# Sonar_Power_Schematic_LT1962.net
KiCad netlist of a schematic drawn in EAGLE
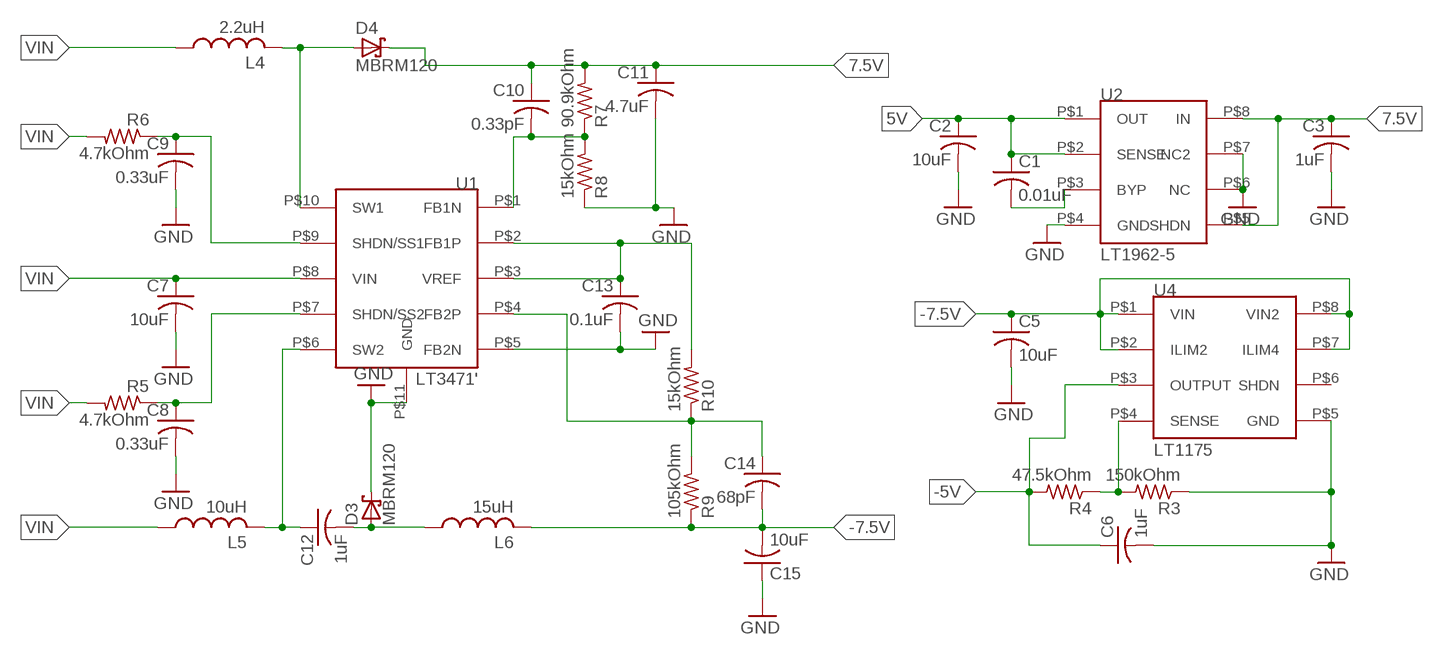
[diagram p0: schematic, sheet 1]

(export (version "E")
  (design (tool "Eeschema 10.0.6"))
  (components
    (comp (ref "C1")
      (value "0.01uF")
      (footprint "eagle-import:C0603")
      (libsource (lib "eagle-import") (part "C-USC0603"))
    )
    (comp (ref "C2")
      (value "10uF")
      (footprint "eagle-import:C0603")
      (libsource (lib "eagle-import") (part "C-USC0603"))
    )
    (comp (ref "C3")
      (value "1uF")
      (footprint "eagle-import:C0603")
      (libsource (lib "eagle-import") (part "C-USC0603"))
    )
    (comp (ref "C5")
      (value "10uF")
      (footprint "eagle-import:C0603")
      (libsource (lib "eagle-import") (part "C-USC0603"))
    )
    (comp (ref "C6")
      (value "1uF")
      (footprint "eagle-import:C0603")
      (libsource (lib "eagle-import") (part "C-USC0603"))
    )
    (comp (ref "C7")
      (value "10uF")
      (footprint "eagle-import:C0603")
      (libsource (lib "eagle-import") (part "C-USC0603"))
    )
    (comp (ref "C8")
      (value "0.33uF")
      (footprint "eagle-import:C0603")
      (libsource (lib "eagle-import") (part "C-USC0603"))
    )
    (comp (ref "C9")
      (value "0.33uF")
      (footprint "eagle-import:C0603")
      (libsource (lib "eagle-import") (part "C-USC0603"))
    )
    (comp (ref "C10")
      (value "0.33pF")
      (footprint "eagle-import:C0603")
      (libsource (lib "eagle-import") (part "C-USC0603"))
    )
    (comp (ref "C11")
      (value "4.7uF")
      (footprint "eagle-import:C0603")
      (libsource (lib "eagle-import") (part "C-USC0603"))
    )
    (comp (ref "C12")
      (value "1uF")
      (footprint "eagle-import:C0603")
      (libsource (lib "eagle-import") (part "C-USC0603"))
    )
    (comp (ref "C13")
      (value "0.1uF")
      (footprint "eagle-import:C0603")
      (libsource (lib "eagle-import") (part "C-USC0603"))
    )
    (comp (ref "C14")
      (value "68pF")
      (footprint "eagle-import:C0603")
      (libsource (lib "eagle-import") (part "C-USC0603"))
    )
    (comp (ref "C15")
      (value "10uF")
      (footprint "eagle-import:C0603")
      (libsource (lib "eagle-import") (part "C-USC0603"))
    )
    (comp (ref "D3")
      (value "MBRM120")
      (footprint "eagle-import:DO-216AA")
      (libsource (lib "eagle-import") (part "MBRM120"))
    )
    (comp (ref "D4")
      (value "MBRM120")
      (footprint "eagle-import:DO-216AA")
      (libsource (lib "eagle-import") (part "MBRM120"))
    )
    (comp (ref "L4")
      (value "2.2uH")
      (footprint "eagle-import:NS4.9X4.9")
      (libsource (lib "eagle-import") (part "LQH5BPN2R2N38L"))
    )
    (comp (ref "L5")
      (value "10uH")
      (footprint "eagle-import:NS5X5")
      (libsource (lib "eagle-import") (part "VLS5045EX-100M2"))
    )
    (comp (ref "L6")
      (value "15uH")
      (footprint "eagle-import:NS5X5")
      (libsource (lib "eagle-import") (part "VLS5045EX-150M-CA1"))
    )
    (comp (ref "R3")
      (value "150kOhm")
      (footprint "eagle-import:R0603")
      (libsource (lib "eagle-import") (part "R-US_R0603"))
    )
    (comp (ref "R4")
      (value "47.5kOhm")
      (footprint "eagle-import:R0603")
      (libsource (lib "eagle-import") (part "R-US_R0603"))
    )
    (comp (ref "R5")
      (value "4.7kOhm")
      (footprint "eagle-import:R0603")
      (libsource (lib "eagle-import") (part "R-US_R0603"))
    )
    (comp (ref "R6")
      (value "4.7kOhm")
      (footprint "eagle-import:R0603")
      (libsource (lib "eagle-import") (part "R-US_R0603"))
    )
    (comp (ref "R7")
      (value "90.9kOhm")
      (footprint "eagle-import:R0603")
      (libsource (lib "eagle-import") (part "R-US_R0603"))
    )
    (comp (ref "R8")
      (value "15kOhm")
      (footprint "eagle-import:R0603")
      (libsource (lib "eagle-import") (part "R-US_R0603"))
    )
    (comp (ref "R9")
      (value "105kOhm")
      (footprint "eagle-import:R0603")
      (libsource (lib "eagle-import") (part "R-US_R0603"))
    )
    (comp (ref "R10")
      (value "15kOhm")
      (footprint "eagle-import:R0603")
      (libsource (lib "eagle-import") (part "R-US_R0603"))
    )
    (comp (ref "U1")
      (value "LT3471'")
      (footprint "eagle-import:10-WFDFN")
      (libsource (lib "eagle-import") (part "LT3471'"))
    )
    (comp (ref "U2")
      (value "LT1962-5")
      (footprint "eagle-import:8-MSOP")
      (libsource (lib "eagle-import") (part "LT1962-5"))
    )
    (comp (ref "U4")
      (value "LT1175")
      (footprint "eagle-import:8-SOIC")
      (libsource (lib "eagle-import") (part "LT1175"))
    )
  )
  (nets
    (net (code "1") (name "-5V") (class "Default")
      (node (ref "C6") (pin "1") (pinfunction "1_1") (pintype "passive"))
      (node (ref "R4") (pin "2") (pinfunction "2_2") (pintype "passive"))
      (node (ref "U4") (pin "P$3") (pinfunction "OUTPUT_P$3") (pintype "bidirectional"))
    )
    (net (code "2") (name "-7.5V") (class "Default")
      (node (ref "C14") (pin "2") (pinfunction "2_2") (pintype "passive"))
      (node (ref "C15") (pin "2") (pinfunction "2_2") (pintype "passive"))
      (node (ref "C5") (pin "1") (pinfunction "1_1") (pintype "passive"))
      (node (ref "L6") (pin "P$2") (pinfunction "2_P$2") (pintype "passive"))
      (node (ref "R9") (pin "1") (pinfunction "1_1") (pintype "passive"))
      (node (ref "U4") (pin "P$1") (pinfunction "VIN_P$1") (pintype "power_in"))
      (node (ref "U4") (pin "P$2") (pinfunction "ILIM2_P$2") (pintype "bidirectional"))
      (node (ref "U4") (pin "P$7") (pinfunction "ILIM4_P$7") (pintype "bidirectional"))
      (node (ref "U4") (pin "P$8") (pinfunction "VIN2_P$8") (pintype "power_in"))
    )
    (net (code "3") (name "5V") (class "Default")
      (node (ref "C1") (pin "1") (pinfunction "1_1") (pintype "passive"))
      (node (ref "C2") (pin "1") (pinfunction "1_1") (pintype "passive"))
      (node (ref "U2") (pin "P$1") (pinfunction "OUT_P$1") (pintype "bidirectional"))
      (node (ref "U2") (pin "P$2") (pinfunction "SENSE_P$2") (pintype "bidirectional"))
    )
    (net (code "4") (name "7.5V") (class "Default")
      (node (ref "C10") (pin "1") (pinfunction "1_1") (pintype "passive"))
      (node (ref "C11") (pin "1") (pinfunction "1_1") (pintype "passive"))
      (node (ref "C3") (pin "1") (pinfunction "1_1") (pintype "passive"))
      (node (ref "D4") (pin "P$1") (pinfunction "C_P$1") (pintype "passive"))
      (node (ref "R7") (pin "2") (pinfunction "2_2") (pintype "passive"))
      (node (ref "U2") (pin "P$5") (pinfunction "SHDN_P$5") (pintype "bidirectional"))
      (node (ref "U2") (pin "P$8") (pinfunction "IN_P$8") (pintype "bidirectional"))
    )
    (net (code "5") (name "GND") (class "Default")
      (node (ref "C11") (pin "2") (pinfunction "2_2") (pintype "passive"))
      (node (ref "C13") (pin "2") (pinfunction "2_2") (pintype "passive"))
      (node (ref "C15") (pin "1") (pinfunction "1_1") (pintype "passive"))
      (node (ref "C2") (pin "2") (pinfunction "2_2") (pintype "passive"))
      (node (ref "C3") (pin "2") (pinfunction "2_2") (pintype "passive"))
      (node (ref "C5") (pin "2") (pinfunction "2_2") (pintype "passive"))
      (node (ref "C6") (pin "2") (pinfunction "2_2") (pintype "passive"))
      (node (ref "C7") (pin "2") (pinfunction "2_2") (pintype "passive"))
      (node (ref "C8") (pin "2") (pinfunction "2_2") (pintype "passive"))
      (node (ref "C9") (pin "2") (pinfunction "2_2") (pintype "passive"))
      (node (ref "D3") (pin "P$1") (pinfunction "C_P$1") (pintype "passive"))
      (node (ref "R3") (pin "1") (pinfunction "1_1") (pintype "passive"))
      (node (ref "R8") (pin "1") (pinfunction "1_1") (pintype "passive"))
      (node (ref "U1") (pin "P$11") (pinfunction "GND_P$11") (pintype "power_in"))
      (node (ref "U1") (pin "P$5") (pinfunction "FB2N_P$5") (pintype "bidirectional"))
      (node (ref "U2") (pin "P$4") (pinfunction "GND_P$4") (pintype "bidirectional"))
      (node (ref "U2") (pin "P$6") (pinfunction "NC_P$6") (pintype "bidirectional"))
      (node (ref "U2") (pin "P$7") (pinfunction "NC2_P$7") (pintype "bidirectional"))
      (node (ref "U4") (pin "P$5") (pinfunction "GND_P$5") (pintype "power_in"))
    )
    (net (code "6") (name "Net-(D3-A)") (class "Default")
      (node (ref "C12") (pin "2") (pinfunction "2_2") (pintype "passive"))
      (node (ref "D3") (pin "P$2") (pinfunction "A_P$2") (pintype "passive"))
      (node (ref "L6") (pin "P$1") (pinfunction "1_P$1") (pintype "passive"))
    )
    (net (code "7") (name "Net-(D4-A)") (class "Default")
      (node (ref "D4") (pin "P$2") (pinfunction "A_P$2") (pintype "passive"))
      (node (ref "L4") (pin "P$2") (pinfunction "2_P$2") (pintype "passive"))
      (node (ref "U1") (pin "P$10") (pinfunction "SW1_P$10") (pintype "bidirectional"))
    )
    (net (code "8") (name "Net-(L5-2)") (class "Default")
      (node (ref "C12") (pin "1") (pinfunction "1_1") (pintype "passive"))
      (node (ref "L5") (pin "P$2") (pinfunction "2_P$2") (pintype "passive"))
      (node (ref "U1") (pin "P$6") (pinfunction "SW2_P$6") (pintype "bidirectional"))
    )
    (net (code "9") (name "Net-(U1-FB1N)") (class "Default")
      (node (ref "C10") (pin "2") (pinfunction "2_2") (pintype "passive"))
      (node (ref "R7") (pin "1") (pinfunction "1_1") (pintype "passive"))
      (node (ref "R8") (pin "2") (pinfunction "2_2") (pintype "passive"))
      (node (ref "U1") (pin "P$1") (pinfunction "FB1N_P$1") (pintype "bidirectional"))
    )
    (net (code "10") (name "Net-(U1-FB1P)") (class "Default")
      (node (ref "C13") (pin "1") (pinfunction "1_1") (pintype "passive"))
      (node (ref "R10") (pin "2") (pinfunction "2_2") (pintype "passive"))
      (node (ref "U1") (pin "P$2") (pinfunction "FB1P_P$2") (pintype "bidirectional"))
      (node (ref "U1") (pin "P$3") (pinfunction "VREF_P$3") (pintype "power_in"))
    )
    (net (code "11") (name "Net-(U1-FB2P)") (class "Default")
      (node (ref "C14") (pin "1") (pinfunction "1_1") (pintype "passive"))
      (node (ref "R10") (pin "1") (pinfunction "1_1") (pintype "passive"))
      (node (ref "R9") (pin "2") (pinfunction "2_2") (pintype "passive"))
      (node (ref "U1") (pin "P$4") (pinfunction "FB2P_P$4") (pintype "bidirectional"))
    )
    (net (code "12") (name "Net-(U1-SHDN{slash}SS1)") (class "Default")
      (node (ref "C9") (pin "1") (pinfunction "1_1") (pintype "passive"))
      (node (ref "R6") (pin "1") (pinfunction "1_1") (pintype "passive"))
      (node (ref "U1") (pin "P$9") (pinfunction "SHDN/SS1_P$9") (pintype "bidirectional"))
    )
    (net (code "13") (name "Net-(U1-SHDN{slash}SS2)") (class "Default")
      (node (ref "C8") (pin "1") (pinfunction "1_1") (pintype "passive"))
      (node (ref "R5") (pin "1") (pinfunction "1_1") (pintype "passive"))
      (node (ref "U1") (pin "P$7") (pinfunction "SHDN/SS2_P$7") (pintype "bidirectional"))
    )
    (net (code "14") (name "Net-(U2-BYP)") (class "Default")
      (node (ref "C1") (pin "2") (pinfunction "2_2") (pintype "passive"))
      (node (ref "U2") (pin "P$3") (pinfunction "BYP_P$3") (pintype "bidirectional"))
    )
    (net (code "15") (name "Net-(U4-SENSE)") (class "Default")
      (node (ref "R3") (pin "2") (pinfunction "2_2") (pintype "passive"))
      (node (ref "R4") (pin "1") (pinfunction "1_1") (pintype "passive"))
      (node (ref "U4") (pin "P$4") (pinfunction "SENSE_P$4") (pintype "bidirectional"))
    )
    (net (code "16") (name "VIN") (class "Default")
      (node (ref "C7") (pin "1") (pinfunction "1_1") (pintype "passive"))
      (node (ref "L4") (pin "P$1") (pinfunction "1_P$1") (pintype "passive"))
      (node (ref "L5") (pin "P$1") (pinfunction "1_P$1") (pintype "passive"))
      (node (ref "R5") (pin "2") (pinfunction "2_2") (pintype "passive"))
      (node (ref "R6") (pin "2") (pinfunction "2_2") (pintype "passive"))
      (node (ref "U1") (pin "P$8") (pinfunction "VIN_P$8") (pintype "power_in"))
    )
    (net (code "17") (name "unconnected-(U4-SHDN-PadP$6)") (class "Default")
      (node (ref "U4") (pin "P$6") (pinfunction "SHDN_P$6") (pintype "bidirectional"))
    )
  )
)
